# lisa_ui.net
KiCad netlist of a schematic drawn in EAGLE
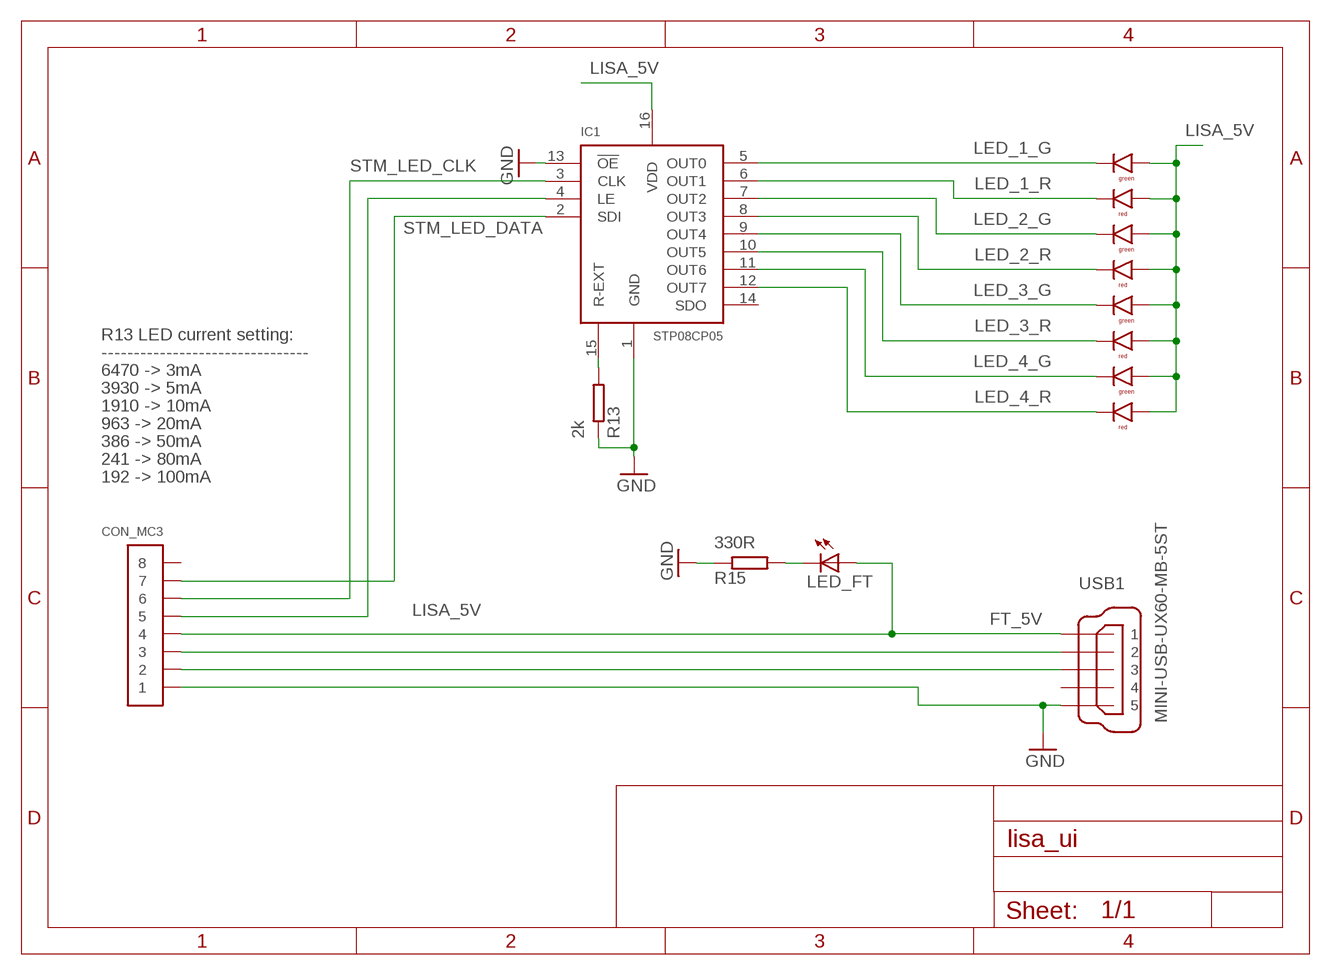
[diagram p0: schematic, sheet 1]

(export (version "E")
  (design (tool "Eeschema 10.0.6"))
  (components
    (comp (ref "CON_MC3")
      (value "CONN_8-1")
      (footprint "eagle-import:PB-53261-08")
      (libsource (lib "eagle-import") (part "CONN_8-1"))
    )
    (comp (ref "IC1")
      (value "STP08CP05")
      (footprint "eagle-import:TSSOP16")
      (libsource (lib "eagle-import") (part "STP08CP05"))
    )
    (comp (ref "LED_1")
      (value "LED_DUO")
      (footprint "eagle-import:DUO_LED")
      (libsource (lib "eagle-import") (part "LED_DUO"))
    )
    (comp (ref "LED_2")
      (value "LED_DUO")
      (footprint "eagle-import:DUO_LED")
      (libsource (lib "eagle-import") (part "LED_DUO"))
    )
    (comp (ref "LED_3")
      (value "LED_DUO")
      (footprint "eagle-import:DUO_LED")
      (libsource (lib "eagle-import") (part "LED_DUO"))
    )
    (comp (ref "LED_4")
      (value "LED_DUO")
      (footprint "eagle-import:DUO_LED")
      (libsource (lib "eagle-import") (part "LED_DUO"))
    )
    (comp (ref "LED_FT")
      (value "LED-0603")
      (footprint "eagle-import:0603-LED")
      (libsource (lib "eagle-import") (part "LED-0603"))
    )
    (comp (ref "R13")
      (value "2k")
      (footprint "eagle-import:0603-RES")
      (libsource (lib "eagle-import") (part "RESISTOR-0603"))
    )
    (comp (ref "R15")
      (value "330R")
      (footprint "eagle-import:0603-RES")
      (libsource (lib "eagle-import") (part "RESISTOR-0603"))
    )
    (comp (ref "USB1")
      (value "MINI-USB-UX60-MB-5ST")
      (footprint "eagle-import:UX60-MB-5ST")
      (libsource (lib "eagle-import") (part "MINI-USB-UX60-MB-5ST"))
    )
  )
  (nets
    (net (code "1") (name "/FT_5V") (class "Default")
      (node (ref "CON_MC3") (pin "4") (pinfunction "4_4") (pintype "bidirectional"))
      (node (ref "LED_FT") (pin "A") (pinfunction "A_A") (pintype "passive"))
      (node (ref "USB1") (pin "1") (pinfunction "1_1") (pintype "input"))
    )
    (net (code "2") (name "/LED_1_G") (class "Default")
      (node (ref "IC1") (pin "5") (pinfunction "OUT0_5") (pintype "bidirectional"))
      (node (ref "LED_1") (pin "3") (pinfunction "P$3_3") (pintype "bidirectional"))
    )
    (net (code "3") (name "/LED_1_R") (class "Default")
      (node (ref "IC1") (pin "6") (pinfunction "OUT1_6") (pintype "bidirectional"))
      (node (ref "LED_1") (pin "2") (pinfunction "P$2_2") (pintype "bidirectional"))
    )
    (net (code "4") (name "/LED_2_G") (class "Default")
      (node (ref "IC1") (pin "7") (pinfunction "OUT2_7") (pintype "bidirectional"))
      (node (ref "LED_2") (pin "3") (pinfunction "P$3_3") (pintype "bidirectional"))
    )
    (net (code "5") (name "/LED_2_R") (class "Default")
      (node (ref "IC1") (pin "8") (pinfunction "OUT3_8") (pintype "bidirectional"))
      (node (ref "LED_2") (pin "2") (pinfunction "P$2_2") (pintype "bidirectional"))
    )
    (net (code "6") (name "/LED_3_G") (class "Default")
      (node (ref "IC1") (pin "9") (pinfunction "OUT4_9") (pintype "bidirectional"))
      (node (ref "LED_3") (pin "3") (pinfunction "P$3_3") (pintype "bidirectional"))
    )
    (net (code "7") (name "/LED_3_R") (class "Default")
      (node (ref "IC1") (pin "10") (pinfunction "OUT5_10") (pintype "bidirectional"))
      (node (ref "LED_3") (pin "2") (pinfunction "P$2_2") (pintype "bidirectional"))
    )
    (net (code "8") (name "/LED_4_G") (class "Default")
      (node (ref "IC1") (pin "11") (pinfunction "OUT6_11") (pintype "bidirectional"))
      (node (ref "LED_4") (pin "3") (pinfunction "P$3_3") (pintype "bidirectional"))
    )
    (net (code "9") (name "/LED_4_R") (class "Default")
      (node (ref "IC1") (pin "12") (pinfunction "OUT7_12") (pintype "bidirectional"))
      (node (ref "LED_4") (pin "2") (pinfunction "P$2_2") (pintype "bidirectional"))
    )
    (net (code "10") (name "/LISA_5V") (class "Default")
      (node (ref "CON_MC3") (pin "5") (pinfunction "5_5") (pintype "bidirectional"))
      (node (ref "IC1") (pin "16") (pinfunction "VDD_16") (pintype "bidirectional"))
      (node (ref "IC1") (pin "4") (pinfunction "LE_4") (pintype "bidirectional"))
      (node (ref "LED_1") (pin "1") (pinfunction "P$1_1") (pintype "bidirectional"))
      (node (ref "LED_1") (pin "4") (pinfunction "P$4_4") (pintype "bidirectional"))
      (node (ref "LED_2") (pin "1") (pinfunction "P$1_1") (pintype "bidirectional"))
      (node (ref "LED_2") (pin "4") (pinfunction "P$4_4") (pintype "bidirectional"))
      (node (ref "LED_3") (pin "1") (pinfunction "P$1_1") (pintype "bidirectional"))
      (node (ref "LED_3") (pin "4") (pinfunction "P$4_4") (pintype "bidirectional"))
      (node (ref "LED_4") (pin "1") (pinfunction "P$1_1") (pintype "bidirectional"))
      (node (ref "LED_4") (pin "4") (pinfunction "P$4_4") (pintype "bidirectional"))
    )
    (net (code "11") (name "/STM_LED_CLK") (class "Default")
      (node (ref "CON_MC3") (pin "6") (pinfunction "6_6") (pintype "bidirectional"))
      (node (ref "IC1") (pin "3") (pinfunction "CLK_3") (pintype "bidirectional"))
    )
    (net (code "12") (name "/STM_LED_DATA") (class "Default")
      (node (ref "CON_MC3") (pin "7") (pinfunction "7_7") (pintype "bidirectional"))
      (node (ref "IC1") (pin "2") (pinfunction "SDI_2") (pintype "bidirectional"))
    )
    (net (code "13") (name "GND") (class "Default")
      (node (ref "CON_MC3") (pin "1") (pinfunction "1_1") (pintype "bidirectional"))
      (node (ref "IC1") (pin "1") (pinfunction "GND_1") (pintype "bidirectional"))
      (node (ref "IC1") (pin "13") (pinfunction "~{OE}_13") (pintype "bidirectional"))
      (node (ref "R13") (pin "P$1") (pinfunction "1_P$1") (pintype "passive"))
      (node (ref "R15") (pin "P$1") (pinfunction "1_P$1") (pintype "passive"))
      (node (ref "USB1") (pin "5") (pinfunction "5_5") (pintype "input"))
    )
    (net (code "14") (name "Net-(CON_MC3-Pad2)") (class "Default")
      (node (ref "CON_MC3") (pin "2") (pinfunction "2_2") (pintype "bidirectional"))
      (node (ref "USB1") (pin "3") (pinfunction "3_3") (pintype "input"))
    )
    (net (code "15") (name "Net-(CON_MC3-Pad3)") (class "Default")
      (node (ref "CON_MC3") (pin "3") (pinfunction "3_3") (pintype "bidirectional"))
      (node (ref "USB1") (pin "2") (pinfunction "2_2") (pintype "input"))
    )
    (net (code "16") (name "Net-(IC1-R-EXT)") (class "Default")
      (node (ref "IC1") (pin "15") (pinfunction "R-EXT_15") (pintype "bidirectional"))
      (node (ref "R13") (pin "P$2") (pinfunction "2_P$2") (pintype "passive"))
    )
    (net (code "17") (name "Net-(R15-2)") (class "Default")
      (node (ref "LED_FT") (pin "C") (pinfunction "C_C") (pintype "passive"))
      (node (ref "R15") (pin "P$2") (pinfunction "2_P$2") (pintype "passive"))
    )
    (net (code "18") (name "unconnected-(CON_MC3-Pad8)") (class "Default")
      (node (ref "CON_MC3") (pin "8") (pinfunction "8_8") (pintype "bidirectional"))
    )
    (net (code "19") (name "unconnected-(IC1-SDO-Pad14)") (class "Default")
      (node (ref "IC1") (pin "14") (pinfunction "SDO_14") (pintype "bidirectional"))
    )
    (net (code "20") (name "unconnected-(USB1-Pad4)") (class "Default")
      (node (ref "USB1") (pin "4") (pinfunction "4_4") (pintype "input"))
    )
  )
)
